# FOC.net
KiCad netlist of a schematic drawn in Altium Designer
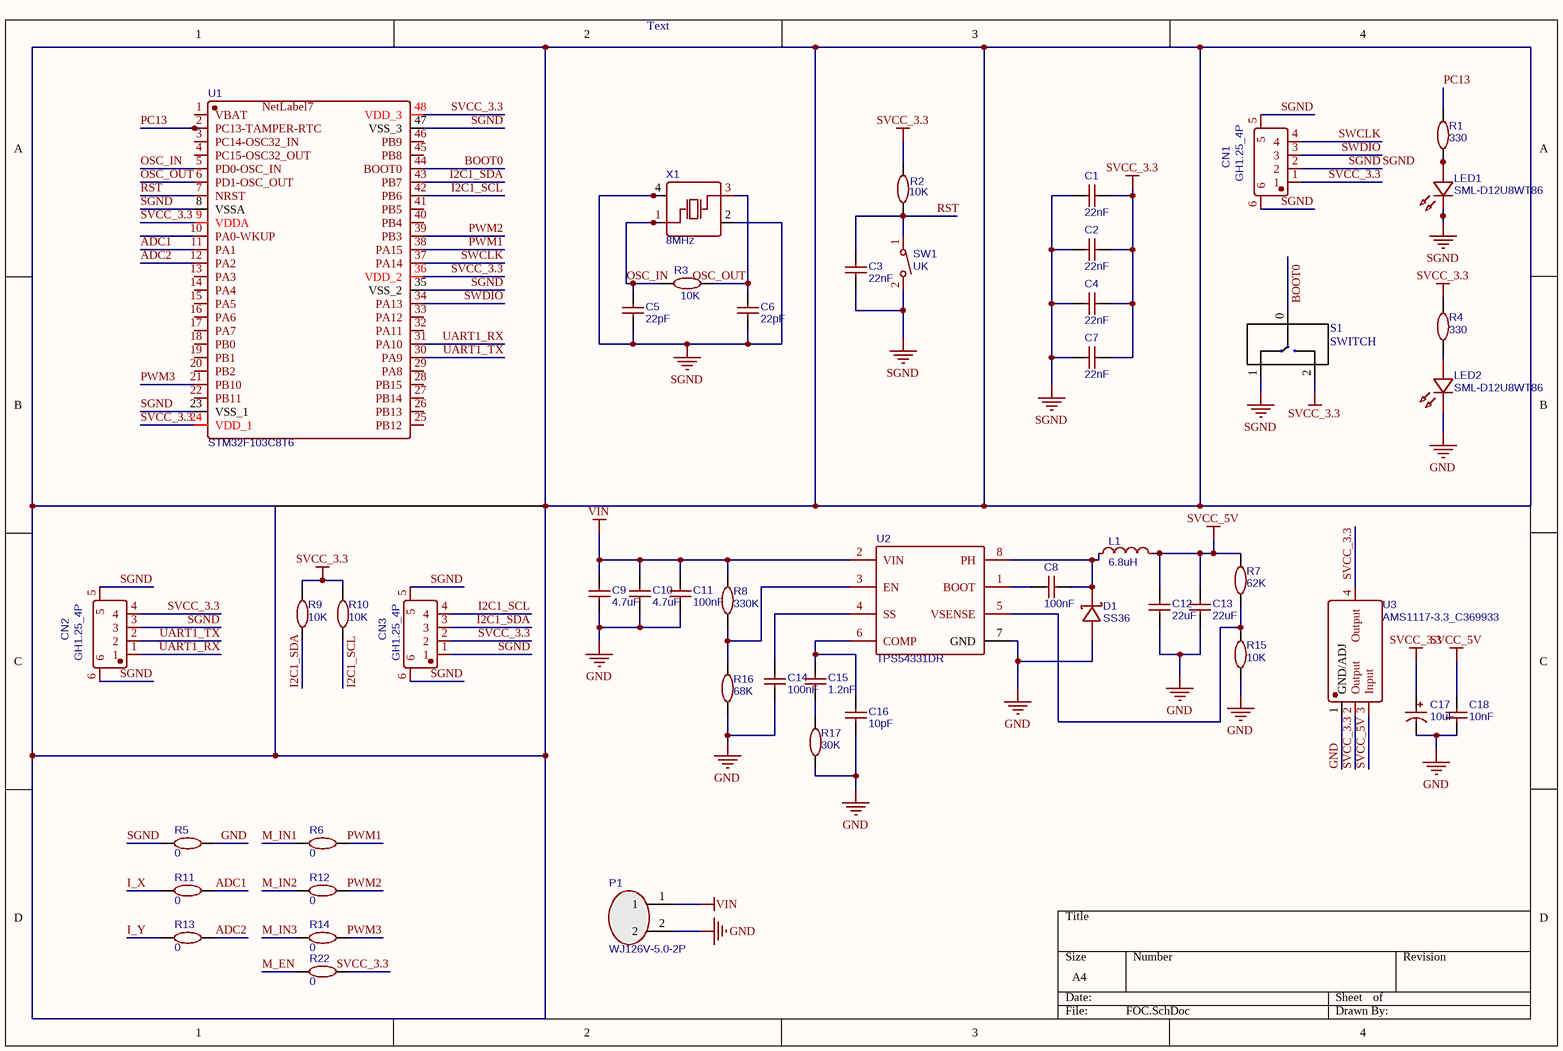
[diagram p0: FOC.SchDoc]

(export (version "E")
  (design (tool "Eeschema 10.0.6"))
  (components
    (comp (ref "C1")
      (value "22nF")
      (footprint "C0603")
      (fields
        (field (name "BOM_MANUFACTURER PART") "CC0805KRX7R9BB104")
        (field (name "BOM_SUPPLIER PART") "C49678")
      )
      (libsource (lib "FOC") (part "22nF"))
    )
    (comp (ref "C2")
      (value "22nF")
      (footprint "C0603")
      (fields
        (field (name "BOM_MANUFACTURER PART") "CC0805KRX7R9BB104")
        (field (name "BOM_SUPPLIER PART") "C49678")
      )
      (libsource (lib "FOC") (part "22nF"))
    )
    (comp (ref "C3")
      (value "22nF")
      (footprint "C0603")
      (fields
        (field (name "BOM_MANUFACTURER PART") "CC0805KRX7R9BB104")
        (field (name "BOM_SUPPLIER PART") "C49678")
      )
      (libsource (lib "FOC") (part "22nF"))
    )
    (comp (ref "C4")
      (value "22nF")
      (footprint "C0603")
      (fields
        (field (name "BOM_MANUFACTURER PART") "CC0805KRX7R9BB104")
        (field (name "BOM_SUPPLIER PART") "C49678")
      )
      (libsource (lib "FOC") (part "22nF"))
    )
    (comp (ref "C5")
      (value "22pF")
      (footprint "C0603")
      (fields
        (field (name "BOM_MANUFACTURER PART") "CC0805KRX7R9BB104")
        (field (name "BOM_SUPPLIER PART") "C49678")
      )
      (libsource (lib "FOC") (part "22pF"))
    )
    (comp (ref "C6")
      (value "22pF")
      (footprint "C0603")
      (fields
        (field (name "BOM_MANUFACTURER PART") "CC0805KRX7R9BB104")
        (field (name "BOM_SUPPLIER PART") "C49678")
      )
      (libsource (lib "FOC") (part "22pF"))
    )
    (comp (ref "C7")
      (value "22nF")
      (footprint "C0603")
      (fields
        (field (name "BOM_MANUFACTURER PART") "CC0805KRX7R9BB104")
        (field (name "BOM_SUPPLIER PART") "C49678")
      )
      (libsource (lib "FOC") (part "22nF"))
    )
    (comp (ref "C8")
      (value "100nF")
      (footprint "C0603")
      (fields
        (field (name "BOM_MANUFACTURER PART") "CC0805KRX7R9BB104")
        (field (name "BOM_SUPPLIER PART") "C49678")
      )
      (libsource (lib "FOC") (part "100nF"))
    )
    (comp (ref "C9")
      (value "4.7uF")
      (footprint "C0603")
      (fields
        (field (name "BOM_MANUFACTURER PART") "CC0805KRX7R9BB104")
        (field (name "BOM_SUPPLIER PART") "C49678")
      )
      (libsource (lib "FOC") (part "4.7uF"))
    )
    (comp (ref "C10")
      (value "4.7uF")
      (footprint "C0603")
      (fields
        (field (name "BOM_MANUFACTURER PART") "CC0805KRX7R9BB104")
        (field (name "BOM_SUPPLIER PART") "C49678")
      )
      (libsource (lib "FOC") (part "4.7uF"))
    )
    (comp (ref "C11")
      (value "100nF")
      (footprint "C0603")
      (fields
        (field (name "BOM_MANUFACTURER PART") "CC0805KRX7R9BB104")
        (field (name "BOM_SUPPLIER PART") "C49678")
      )
      (libsource (lib "FOC") (part "100nF"))
    )
    (comp (ref "C12")
      (value "22uF")
      (footprint "C0603")
      (fields
        (field (name "BOM_MANUFACTURER PART") "CC0805KRX7R9BB104")
        (field (name "BOM_SUPPLIER PART") "C49678")
      )
      (libsource (lib "FOC") (part "22uF"))
    )
    (comp (ref "C13")
      (value "22uF")
      (footprint "C0603")
      (fields
        (field (name "BOM_MANUFACTURER PART") "CC0805KRX7R9BB104")
        (field (name "BOM_SUPPLIER PART") "C49678")
      )
      (libsource (lib "FOC") (part "22uF"))
    )
    (comp (ref "C14")
      (value "100nF")
      (footprint "C0603")
      (fields
        (field (name "BOM_MANUFACTURER PART") "CC0805KRX7R9BB104")
        (field (name "BOM_SUPPLIER PART") "C49678")
      )
      (libsource (lib "FOC") (part "100nF"))
    )
    (comp (ref "C15")
      (value "1.2nF")
      (footprint "C0603")
      (fields
        (field (name "BOM_MANUFACTURER PART") "CC0805KRX7R9BB104")
        (field (name "BOM_SUPPLIER PART") "C49678")
      )
      (libsource (lib "FOC") (part "1.2nF"))
    )
    (comp (ref "C16")
      (value "10pF")
      (footprint "C0603")
      (fields
        (field (name "BOM_MANUFACTURER PART") "CC0805KRX7R9BB104")
        (field (name "BOM_SUPPLIER PART") "C49678")
      )
      (libsource (lib "FOC") (part "10pF"))
    )
    (comp (ref "C17")
      (value "10uF")
      (footprint "CAP-SMD_L3.2-W1.6-RD")
      (description "tan")
      (fields
        (field (name "BOM_MANUFACTURER PART") "CA45-A016K106T")
        (field (name "BOM_SUPPLIER PART") "C119051")
        (field (name "CONTRIBUTOR") "LCSC")
      )
      (libsource (lib "FOC") (part "10uF"))
    )
    (comp (ref "C18")
      (value "10nF")
      (footprint "C0603")
      (fields
        (field (name "BOM_MANUFACTURER PART") "CC0805KRX7R9BB104")
        (field (name "BOM_SUPPLIER PART") "C49678")
      )
      (libsource (lib "FOC") (part "10nF"))
    )
    (comp (ref "CN1")
      (value "GH1.25_4P")
      (footprint "CONN-TH_4P-P1.25_HRS_DF13-4P-1.25H-21")
      (fields
        (field (name "BOM_SUPPLIER PART") "C597872")
        (field (name "BOM_MANUFACTURER PART") "DF13-4P-1.25H(21)")
        (field (name "CONTRIBUTOR") "LCSC")
      )
      (libsource (lib "FOC") (part "GH1.25_4P"))
    )
    (comp (ref "CN2")
      (value "GH1.25_4P")
      (footprint "CONN-TH_4P-P1.25_HRS_DF13-4P-1.25H-21")
      (fields
        (field (name "BOM_SUPPLIER PART") "C597872")
        (field (name "BOM_MANUFACTURER PART") "DF13-4P-1.25H(21)")
        (field (name "CONTRIBUTOR") "LCSC")
      )
      (libsource (lib "FOC") (part "GH1.25_4P"))
    )
    (comp (ref "CN3")
      (value "GH1.25_4P")
      (footprint "CONN-TH_4P-P1.25_HRS_DF13-4P-1.25H-21")
      (fields
        (field (name "BOM_SUPPLIER PART") "C597872")
        (field (name "BOM_MANUFACTURER PART") "DF13-4P-1.25H(21)")
        (field (name "CONTRIBUTOR") "LCSC")
      )
      (libsource (lib "FOC") (part "GH1.25_4P"))
    )
    (comp (ref "D1")
      (value "SS36")
      (footprint "SMA_L4.3-W2.6-LS5.2-RD")
      (fields (field (name "BOM_SUPPLIER PART") "C16015"))
      (libsource (lib "FOC") (part "SS36"))
    )
    (comp (ref "L1")
      (value "6.8uH")
      (footprint "IND-SMD_L5.0-W5.0_SWPA5040S")
      (fields
        (field (name "BOM_MANUFACTURER PART") "SWPA5040S6R8M")
        (field (name "BOM_SUPPLIER PART") "C36411")
      )
      (libsource (lib "FOC") (part "6.8uH"))
    )
    (comp (ref "LED1")
      (value "SML-D12U8WT86")
      (footprint "LED0603-RD")
      (description "0603")
      (fields (field (name "BOM_SUPPLIER PART") "C510027") (field (name "CONTRIBUTOR") "LCSC"))
      (libsource (lib "FOC") (part "LED_1"))
    )
    (comp (ref "LED2")
      (value "SML-D12U8WT86")
      (footprint "LED0603-RD")
      (description "0603")
      (fields (field (name "BOM_SUPPLIER PART") "C510027") (field (name "CONTRIBUTOR") "LCSC"))
      (libsource (lib "FOC") (part "LED_1"))
    )
    (comp (ref "P1")
      (value "WJ126V-5.0-2P")
      (footprint "CONN-TH_WJ126V-5.0-2P")
      (fields (field (name "BOM_SUPPLIER PART") "C8404"))
      (libsource (lib "FOC") (part "WJ126V-5.0-2P"))
    )
    (comp (ref "R1")
      (value "330")
      (footprint "C0603")
      (fields
        (field (name "BOM_MANUFACTURER PART") "0805W8F1002T5E")
        (field (name "BOM_SUPPLIER PART") "C17414")
      )
      (libsource (lib "FOC") (part "330"))
    )
    (comp (ref "R2")
      (value "10K")
      (footprint "R0603")
      (fields
        (field (name "BOM_MANUFACTURER PART") "0805W8F1002T5E")
        (field (name "BOM_SUPPLIER PART") "C17414")
      )
      (libsource (lib "FOC") (part "10K"))
    )
    (comp (ref "R3")
      (value "10K")
      (footprint "R0603")
      (fields
        (field (name "BOM_MANUFACTURER PART") "0805W8F1002T5E")
        (field (name "BOM_SUPPLIER PART") "C17414")
      )
      (libsource (lib "FOC") (part "10K"))
    )
    (comp (ref "R4")
      (value "330")
      (footprint "C0603")
      (fields
        (field (name "BOM_MANUFACTURER PART") "0805W8F1002T5E")
        (field (name "BOM_SUPPLIER PART") "C17414")
      )
      (libsource (lib "FOC") (part "330"))
    )
    (comp (ref "R5")
      (value "0")
      (footprint "R0603")
      (description "0欧电阻")
      (fields
        (field (name "BOM_MANUFACTURER PART") "0805W8F1002T5E")
        (field (name "BOM_SUPPLIER PART") "C17414")
      )
      (libsource (lib "FOC") (part "0"))
    )
    (comp (ref "R6")
      (value "0")
      (footprint "R0603")
      (description "0欧电阻")
      (fields
        (field (name "BOM_MANUFACTURER PART") "0805W8F1002T5E")
        (field (name "BOM_SUPPLIER PART") "C17414")
      )
      (libsource (lib "FOC") (part "0"))
    )
    (comp (ref "R7")
      (value "62K")
      (footprint "R0603")
      (fields
        (field (name "BOM_MANUFACTURER PART") "0805W8F1002T5E")
        (field (name "BOM_SUPPLIER PART") "C17414")
      )
      (libsource (lib "FOC") (part "62K"))
    )
    (comp (ref "R8")
      (value "330K")
      (footprint "R0603")
      (description "R0603")
      (fields
        (field (name "BOM_MANUFACTURER PART") "0603WAF3303T5E")
        (field (name "BOM_SUPPLIER PART") "C23137")
      )
      (libsource (lib "FOC") (part "330K"))
    )
    (comp (ref "R9")
      (value "10K")
      (footprint "R0603")
      (fields
        (field (name "BOM_MANUFACTURER PART") "0805W8F1002T5E")
        (field (name "BOM_SUPPLIER PART") "C17414")
      )
      (libsource (lib "FOC") (part "10K"))
    )
    (comp (ref "R10")
      (value "10K")
      (footprint "R0603")
      (fields
        (field (name "BOM_MANUFACTURER PART") "0805W8F1002T5E")
        (field (name "BOM_SUPPLIER PART") "C17414")
      )
      (libsource (lib "FOC") (part "10K"))
    )
    (comp (ref "R11")
      (value "0")
      (footprint "R0603")
      (description "0欧电阻")
      (fields
        (field (name "BOM_MANUFACTURER PART") "0805W8F1002T5E")
        (field (name "BOM_SUPPLIER PART") "C17414")
      )
      (libsource (lib "FOC") (part "0"))
    )
    (comp (ref "R12")
      (value "0")
      (footprint "R0603")
      (description "0欧电阻")
      (fields
        (field (name "BOM_MANUFACTURER PART") "0805W8F1002T5E")
        (field (name "BOM_SUPPLIER PART") "C17414")
      )
      (libsource (lib "FOC") (part "0"))
    )
    (comp (ref "R13")
      (value "0")
      (footprint "R0603")
      (description "0欧电阻")
      (fields
        (field (name "BOM_MANUFACTURER PART") "0805W8F1002T5E")
        (field (name "BOM_SUPPLIER PART") "C17414")
      )
      (libsource (lib "FOC") (part "0"))
    )
    (comp (ref "R14")
      (value "0")
      (footprint "R0603")
      (description "0欧电阻")
      (fields
        (field (name "BOM_MANUFACTURER PART") "0805W8F1002T5E")
        (field (name "BOM_SUPPLIER PART") "C17414")
      )
      (libsource (lib "FOC") (part "0"))
    )
    (comp (ref "R15")
      (value "10K")
      (footprint "R0603")
      (fields
        (field (name "BOM_MANUFACTURER PART") "0805W8F1002T5E")
        (field (name "BOM_SUPPLIER PART") "C17414")
      )
      (libsource (lib "FOC") (part "10K"))
    )
    (comp (ref "R16")
      (value "68K")
      (footprint "R0603")
      (fields
        (field (name "BOM_MANUFACTURER PART") "0805W8F1002T5E")
        (field (name "BOM_SUPPLIER PART") "C17414")
      )
      (libsource (lib "FOC") (part "68K"))
    )
    (comp (ref "R17")
      (value "30K")
      (footprint "R0603")
      (fields
        (field (name "BOM_MANUFACTURER PART") "0805W8F1002T5E")
        (field (name "BOM_SUPPLIER PART") "C17414")
      )
      (libsource (lib "FOC") (part "30K"))
    )
    (comp (ref "R22")
      (value "0")
      (footprint "R0603")
      (description "0欧电阻")
      (fields
        (field (name "BOM_MANUFACTURER PART") "0805W8F1002T5E")
        (field (name "BOM_SUPPLIER PART") "C17414")
      )
      (libsource (lib "FOC") (part "0"))
    )
    (comp (ref "S1") (value "SWITCH") (footprint "switch") (libsource (lib "FOC") (part "SWITCH")))
    (comp (ref "SW1")
      (value "UK")
      (footprint "SW-TH_L6.0-W3.5-P6.50")
      (fields
        (field (name "BOM_SUPPLIER PART") "C493223")
        (field (name "BOM_MANUFACTURER PART") "UK-B0205G43-DP25Y")
        (field (name "CONTRIBUTOR") "LCSC")
      )
      (libsource (lib "FOC") (part "UK-B0205G43-DP25Y"))
    )
    (comp (ref "U1")
      (value "STM32F103C8T6")
      (footprint "LQFP-48_L7.0-W7.0-P0.50-LS9.0-BL")
      (fields (field (name "BOM_SUPPLIER PART") "C8734"))
      (libsource (lib "FOC") (part "STM32F103C8T6"))
    )
    (comp (ref "U2")
      (value "TPS54331DR")
      (footprint "SOIC-8_L5.0-W4.0-P1.27-LS6.0-BL")
      (description "电源芯片")
      (fields (field (name "BOM_SUPPLIER PART") "C9865"))
      (libsource (lib "FOC") (part "TPS54331DR"))
    )
    (comp (ref "U3")
      (value "AMS1117-3.3_C369933")
      (footprint "SOT-223-4_L6.5-W3.5-P2.30-LS7.0-BR")
      (fields
        (field (name "BOM_SUPPLIER PART") "C369933")
        (field (name "BOM_MANUFACTURER PART") "AMS1117-3.3")
        (field (name "CONTRIBUTOR") "LCSC")
      )
      (libsource (lib "FOC") (part "AMS1117-3.3_C369933"))
    )
    (comp (ref "X1")
      (value "8MHz")
      (footprint "CRYSTAL-SMD_4P-L5.0-W3.2-BL")
      (fields
        (field (name "BOM_SUPPLIER PART") "C337573")
        (field (name "BOM_MANUFACTURER PART") "7B08070003")
        (field (name "CONTRIBUTOR") "LCSC")
      )
      (libsource (lib "FOC") (part "8MHz"))
    )
  )
  (nets
    (net (code "1") (name "/ADC1") (class "Default")
      (node (ref "R11") (pin "2") (pinfunction "2_2") (pintype "passive"))
      (node (ref "U1") (pin "11") (pinfunction "PA1_11") (pintype "passive"))
    )
    (net (code "2") (name "/ADC2") (class "Default")
      (node (ref "R13") (pin "2") (pinfunction "2_2") (pintype "passive"))
      (node (ref "U1") (pin "12") (pinfunction "PA2_12") (pintype "passive"))
    )
    (net (code "3") (name "/BOOT0") (class "Default")
      (node (ref "S1") (pin "0") (pinfunction "0_0") (pintype "passive"))
      (node (ref "U1") (pin "44") (pinfunction "BOOT0_44") (pintype "passive"))
    )
    (net (code "4") (name "/I2C1_SCL") (class "Default")
      (node (ref "CN3") (pin "4") (pinfunction "4_4") (pintype "passive"))
      (node (ref "R10") (pin "1") (pinfunction "1_1") (pintype "passive"))
      (node (ref "U1") (pin "42") (pinfunction "PB6_42") (pintype "passive"))
    )
    (net (code "5") (name "/I2C1_SDA") (class "Default")
      (node (ref "CN3") (pin "3") (pinfunction "3_3") (pintype "passive"))
      (node (ref "R9") (pin "1") (pinfunction "1_1") (pintype "passive"))
      (node (ref "U1") (pin "43") (pinfunction "PB7_43") (pintype "passive"))
    )
    (net (code "6") (name "/I_X") (class "Default")
      (node (ref "R11") (pin "1") (pinfunction "1_1") (pintype "passive"))
    )
    (net (code "7") (name "/I_Y") (class "Default")
      (node (ref "R13") (pin "1") (pinfunction "1_1") (pintype "passive"))
    )
    (net (code "8") (name "/M_EN") (class "Default")
      (node (ref "R22") (pin "1") (pinfunction "1_1") (pintype "passive"))
    )
    (net (code "9") (name "/M_IN1") (class "Default")
      (node (ref "R6") (pin "1") (pinfunction "1_1") (pintype "passive"))
    )
    (net (code "10") (name "/M_IN2") (class "Default")
      (node (ref "R12") (pin "1") (pinfunction "1_1") (pintype "passive"))
    )
    (net (code "11") (name "/M_IN3") (class "Default")
      (node (ref "R14") (pin "1") (pinfunction "1_1") (pintype "passive"))
    )
    (net (code "13") (name "/OSC_IN") (class "Default")
      (node (ref "C5") (pin "2") (pinfunction "2_2") (pintype "passive"))
      (node (ref "R3") (pin "1") (pinfunction "1_1") (pintype "passive"))
      (node (ref "U1") (pin "5") (pinfunction "PD0-OSC_IN_5") (pintype "passive"))
      (node (ref "X1") (pin "1") (pinfunction "OSC1_1") (pintype "passive"))
    )
    (net (code "14") (name "/OSC_OUT") (class "Default")
      (node (ref "C6") (pin "2") (pinfunction "2_2") (pintype "passive"))
      (node (ref "R3") (pin "2") (pinfunction "2_2") (pintype "passive"))
      (node (ref "U1") (pin "6") (pinfunction "PD1-OSC_OUT_6") (pintype "passive"))
      (node (ref "X1") (pin "3") (pinfunction "OSC2_3") (pintype "passive"))
    )
    (net (code "15") (name "/PC13") (class "Default")
      (node (ref "R1") (pin "2") (pinfunction "2_2") (pintype "passive"))
      (node (ref "U1") (pin "2") (pinfunction "PC13-TAMPER-RTC_2") (pintype "passive"))
    )
    (net (code "16") (name "/PWM1") (class "Default")
      (node (ref "R6") (pin "2") (pinfunction "2_2") (pintype "passive"))
      (node (ref "U1") (pin "38") (pinfunction "PA15_38") (pintype "passive"))
    )
    (net (code "17") (name "/PWM2") (class "Default")
      (node (ref "R12") (pin "2") (pinfunction "2_2") (pintype "passive"))
      (node (ref "U1") (pin "39") (pinfunction "PB3_39") (pintype "passive"))
    )
    (net (code "18") (name "/PWM3") (class "Default")
      (node (ref "R14") (pin "2") (pinfunction "2_2") (pintype "passive"))
      (node (ref "U1") (pin "21") (pinfunction "PB10_21") (pintype "passive"))
    )
    (net (code "19") (name "/RST") (class "Default")
      (node (ref "C3") (pin "2") (pinfunction "2_2") (pintype "passive"))
      (node (ref "R2") (pin "2") (pinfunction "2_2") (pintype "passive"))
      (node (ref "SW1") (pin "1") (pinfunction "1_1") (pintype "passive"))
      (node (ref "U1") (pin "7") (pinfunction "NRST_7") (pintype "passive"))
    )
    (net (code "20") (name "/SWCLK") (class "Default")
      (node (ref "CN1") (pin "4") (pinfunction "4_4") (pintype "passive"))
      (node (ref "U1") (pin "37") (pinfunction "PA14_37") (pintype "passive"))
    )
    (net (code "21") (name "/SWDIO") (class "Default")
      (node (ref "CN1") (pin "3") (pinfunction "3_3") (pintype "passive"))
      (node (ref "U1") (pin "34") (pinfunction "PA13_34") (pintype "passive"))
    )
    (net (code "22") (name "/UART1_RX") (class "Default")
      (node (ref "CN2") (pin "1") (pinfunction "1_1") (pintype "passive"))
      (node (ref "U1") (pin "31") (pinfunction "PA10_31") (pintype "passive"))
    )
    (net (code "23") (name "/UART1_TX") (class "Default")
      (node (ref "CN2") (pin "2") (pinfunction "2_2") (pintype "passive"))
      (node (ref "U1") (pin "30") (pinfunction "PA9_30") (pintype "passive"))
    )
    (net (code "24") (name "GND") (class "Default")
      (node (ref "C10") (pin "1") (pinfunction "1_1") (pintype "passive"))
      (node (ref "C11") (pin "1") (pinfunction "1_1") (pintype "passive"))
      (node (ref "C12") (pin "1") (pinfunction "1_1") (pintype "passive"))
      (node (ref "C13") (pin "1") (pinfunction "1_1") (pintype "passive"))
      (node (ref "C14") (pin "1") (pinfunction "1_1") (pintype "passive"))
      (node (ref "C16") (pin "1") (pinfunction "1_1") (pintype "passive"))
      (node (ref "C17") (pin "2") (pinfunction "2_2") (pintype "passive"))
      (node (ref "C18") (pin "1") (pinfunction "1_1") (pintype "passive"))
      (node (ref "C9") (pin "1") (pinfunction "1_1") (pintype "passive"))
      (node (ref "D1") (pin "2") (pinfunction "A_2") (pintype "passive"))
      (node (ref "LED2") (pin "1") (pinfunction "K_1") (pintype "passive"))
      (node (ref "P1") (pin "2") (pinfunction "2_2") (pintype "passive"))
      (node (ref "R15") (pin "1") (pinfunction "1_1") (pintype "passive"))
      (node (ref "R16") (pin "1") (pinfunction "1_1") (pintype "passive"))
      (node (ref "R17") (pin "1") (pinfunction "1_1") (pintype "passive"))
      (node (ref "R5") (pin "2") (pinfunction "2_2") (pintype "passive"))
      (node (ref "U2") (pin "7") (pinfunction "GND_7") (pintype "passive"))
      (node (ref "U3") (pin "1") (pinfunction "GND/ADJ_1") (pintype "passive"))
    )
    (net (code "25") (name "Net-(C15-Pad1)") (class "Default")
      (node (ref "C15") (pin "1") (pinfunction "1_1") (pintype "passive"))
      (node (ref "R17") (pin "2") (pinfunction "2_2") (pintype "passive"))
    )
    (net (code "26") (name "Net-(D1-K)") (class "Default")
      (node (ref "C8") (pin "1") (pinfunction "1_1") (pintype "passive"))
      (node (ref "D1") (pin "1") (pinfunction "K_1") (pintype "passive"))
      (node (ref "L1") (pin "1") (pinfunction "1_1") (pintype "passive"))
      (node (ref "U2") (pin "8") (pinfunction "PH_8") (pintype "passive"))
    )
    (net (code "27") (name "Net-(LED1-A)") (class "Default")
      (node (ref "LED1") (pin "2") (pinfunction "A_2") (pintype "passive"))
      (node (ref "R1") (pin "1") (pinfunction "1_1") (pintype "passive"))
    )
    (net (code "28") (name "Net-(LED2-A)") (class "Default")
      (node (ref "LED2") (pin "2") (pinfunction "A_2") (pintype "passive"))
      (node (ref "R4") (pin "1") (pinfunction "1_1") (pintype "passive"))
    )
    (net (code "29") (name "Net-(U2-BOOT)") (class "Default")
      (node (ref "C8") (pin "2") (pinfunction "2_2") (pintype "passive"))
      (node (ref "U2") (pin "1") (pinfunction "BOOT_1") (pintype "passive"))
    )
    (net (code "30") (name "Net-(U2-COMP)") (class "Default")
      (node (ref "C15") (pin "2") (pinfunction "2_2") (pintype "passive"))
      (node (ref "C16") (pin "2") (pinfunction "2_2") (pintype "passive"))
      (node (ref "U2") (pin "6") (pinfunction "COMP_6") (pintype "passive"))
    )
    (net (code "31") (name "Net-(U2-EN)") (class "Default")
      (node (ref "R16") (pin "2") (pinfunction "2_2") (pintype "passive"))
      (node (ref "R8") (pin "1") (pinfunction "1_1") (pintype "passive"))
      (node (ref "U2") (pin "3") (pinfunction "EN_3") (pintype "passive"))
    )
    (net (code "32") (name "Net-(U2-SS)") (class "Default")
      (node (ref "C14") (pin "2") (pinfunction "2_2") (pintype "passive"))
      (node (ref "U2") (pin "4") (pinfunction "SS_4") (pintype "passive"))
    )
    (net (code "33") (name "Net-(U2-VSENSE)") (class "Default")
      (node (ref "R15") (pin "2") (pinfunction "2_2") (pintype "passive"))
      (node (ref "R7") (pin "1") (pinfunction "1_1") (pintype "passive"))
      (node (ref "U2") (pin "5") (pinfunction "VSENSE_5") (pintype "passive"))
    )
    (net (code "34") (name "SGND") (class "Default")
      (node (ref "C1") (pin "1") (pinfunction "1_1") (pintype "passive"))
      (node (ref "C2") (pin "1") (pinfunction "1_1") (pintype "passive"))
      (node (ref "C3") (pin "1") (pinfunction "1_1") (pintype "passive"))
      (node (ref "C4") (pin "1") (pinfunction "1_1") (pintype "passive"))
      (node (ref "C5") (pin "1") (pinfunction "1_1") (pintype "passive"))
      (node (ref "C6") (pin "1") (pinfunction "1_1") (pintype "passive"))
      (node (ref "C7") (pin "1") (pinfunction "1_1") (pintype "passive"))
      (node (ref "CN1") (pin "2") (pinfunction "2_2") (pintype "passive"))
      (node (ref "CN1") (pin "5") (pinfunction "5_5") (pintype "passive"))
      (node (ref "CN1") (pin "6") (pinfunction "6_6") (pintype "passive"))
      (node (ref "CN2") (pin "3") (pinfunction "3_3") (pintype "passive"))
      (node (ref "CN2") (pin "5") (pinfunction "5_5") (pintype "passive"))
      (node (ref "CN2") (pin "6") (pinfunction "6_6") (pintype "passive"))
      (node (ref "CN3") (pin "1") (pinfunction "1_1") (pintype "passive"))
      (node (ref "CN3") (pin "5") (pinfunction "5_5") (pintype "passive"))
      (node (ref "CN3") (pin "6") (pinfunction "6_6") (pintype "passive"))
      (node (ref "LED1") (pin "1") (pinfunction "K_1") (pintype "passive"))
      (node (ref "R5") (pin "1") (pinfunction "1_1") (pintype "passive"))
      (node (ref "S1") (pin "1") (pinfunction "1_1") (pintype "passive"))
      (node (ref "SW1") (pin "2") (pinfunction "2_2") (pintype "passive"))
      (node (ref "U1") (pin "23") (pinfunction "VSS_1_23") (pintype "passive"))
      (node (ref "U1") (pin "35") (pinfunction "VSS_2_35") (pintype "passive"))
      (node (ref "U1") (pin "47") (pinfunction "VSS_3_47") (pintype "passive"))
      (node (ref "U1") (pin "8") (pinfunction "VSSA_8") (pintype "passive"))
      (node (ref "X1") (pin "2") (pinfunction "GND_2") (pintype "passive"))
      (node (ref "X1") (pin "4") (pinfunction "GND_4") (pintype "passive"))
    )
    (net (code "35") (name "SVCC_3.3") (class "Default")
      (node (ref "C1") (pin "2") (pinfunction "2_2") (pintype "passive"))
      (node (ref "C17") (pin "1") (pinfunction "1_1") (pintype "passive"))
      (node (ref "C2") (pin "2") (pinfunction "2_2") (pintype "passive"))
      (node (ref "C4") (pin "2") (pinfunction "2_2") (pintype "passive"))
      (node (ref "C7") (pin "2") (pinfunction "2_2") (pintype "passive"))
      (node (ref "CN1") (pin "1") (pinfunction "1_1") (pintype "passive"))
      (node (ref "CN2") (pin "4") (pinfunction "4_4") (pintype "passive"))
      (node (ref "CN3") (pin "2") (pinfunction "2_2") (pintype "passive"))
      (node (ref "R10") (pin "2") (pinfunction "2_2") (pintype "passive"))
      (node (ref "R2") (pin "1") (pinfunction "1_1") (pintype "passive"))
      (node (ref "R22") (pin "2") (pinfunction "2_2") (pintype "passive"))
      (node (ref "R4") (pin "2") (pinfunction "2_2") (pintype "passive"))
      (node (ref "R9") (pin "2") (pinfunction "2_2") (pintype "passive"))
      (node (ref "S1") (pin "2") (pinfunction "2_2") (pintype "passive"))
      (node (ref "U1") (pin "24") (pinfunction "VDD_1_24") (pintype "passive"))
      (node (ref "U1") (pin "36") (pinfunction "VDD_2_36") (pintype "passive"))
      (node (ref "U1") (pin "48") (pinfunction "VDD_3_48") (pintype "passive"))
      (node (ref "U1") (pin "9") (pinfunction "VDDA_9") (pintype "passive"))
      (node (ref "U3") (pin "2") (pinfunction "Output_2") (pintype "passive"))
      (node (ref "U3") (pin "4") (pinfunction "Output_4") (pintype "passive"))
    )
    (net (code "36") (name "SVCC_5V") (class "Default")
      (node (ref "C12") (pin "2") (pinfunction "2_2") (pintype "passive"))
      (node (ref "C13") (pin "2") (pinfunction "2_2") (pintype "passive"))
      (node (ref "C18") (pin "2") (pinfunction "2_2") (pintype "passive"))
      (node (ref "L1") (pin "2") (pinfunction "2_2") (pintype "passive"))
      (node (ref "R7") (pin "2") (pinfunction "2_2") (pintype "passive"))
      (node (ref "U3") (pin "3") (pinfunction "Input_3") (pintype "passive"))
    )
    (net (code "37") (name "VIN") (class "Default")
      (node (ref "C10") (pin "2") (pinfunction "2_2") (pintype "passive"))
      (node (ref "C11") (pin "2") (pinfunction "2_2") (pintype "passive"))
      (node (ref "C9") (pin "2") (pinfunction "2_2") (pintype "passive"))
      (node (ref "P1") (pin "1") (pinfunction "1_1") (pintype "passive"))
      (node (ref "R8") (pin "2") (pinfunction "2_2") (pintype "passive"))
      (node (ref "U2") (pin "2") (pinfunction "VIN_2") (pintype "passive"))
    )
    (net (code "38") (name "unconnected-(U1-PA0-WKUP-Pad10)") (class "Default")
      (node (ref "U1") (pin "10") (pinfunction "PA0-WKUP_10") (pintype "passive"))
    )
    (net (code "39") (name "unconnected-(U1-PA3-Pad13)") (class "Default")
      (node (ref "U1") (pin "13") (pinfunction "PA3_13") (pintype "passive"))
    )
    (net (code "40") (name "unconnected-(U1-PA4-Pad14)") (class "Default")
      (node (ref "U1") (pin "14") (pinfunction "PA4_14") (pintype "passive"))
    )
    (net (code "41") (name "unconnected-(U1-PA5-Pad15)") (class "Default")
      (node (ref "U1") (pin "15") (pinfunction "PA5_15") (pintype "passive"))
    )
    (net (code "42") (name "unconnected-(U1-PA6-Pad16)") (class "Default")
      (node (ref "U1") (pin "16") (pinfunction "PA6_16") (pintype "passive"))
    )
    (net (code "43") (name "unconnected-(U1-PA7-Pad17)") (class "Default")
      (node (ref "U1") (pin "17") (pinfunction "PA7_17") (pintype "passive"))
    )
    (net (code "44") (name "unconnected-(U1-PA8-Pad29)") (class "Default")
      (node (ref "U1") (pin "29") (pinfunction "PA8_29") (pintype "passive"))
    )
    (net (code "45") (name "unconnected-(U1-PA11-Pad32)") (class "Default")
      (node (ref "U1") (pin "32") (pinfunction "PA11_32") (pintype "passive"))
    )
    (net (code "46") (name "unconnected-(U1-PA12-Pad33)") (class "Default")
      (node (ref "U1") (pin "33") (pinfunction "PA12_33") (pintype "passive"))
    )
    (net (code "47") (name "unconnected-(U1-PB0-Pad18)") (class "Default")
      (node (ref "U1") (pin "18") (pinfunction "PB0_18") (pintype "passive"))
    )
    (net (code "48") (name "unconnected-(U1-PB1-Pad19)") (class "Default")
      (node (ref "U1") (pin "19") (pinfunction "PB1_19") (pintype "passive"))
    )
    (net (code "49") (name "unconnected-(U1-PB2-Pad20)") (class "Default")
      (node (ref "U1") (pin "20") (pinfunction "PB2_20") (pintype "passive"))
    )
    (net (code "50") (name "unconnected-(U1-PB4-Pad40)") (class "Default")
      (node (ref "U1") (pin "40") (pinfunction "PB4_40") (pintype "passive"))
    )
    (net (code "51") (name "unconnected-(U1-PB5-Pad41)") (class "Default")
      (node (ref "U1") (pin "41") (pinfunction "PB5_41") (pintype "passive"))
    )
    (net (code "52") (name "unconnected-(U1-PB8-Pad45)") (class "Default")
      (node (ref "U1") (pin "45") (pinfunction "PB8_45") (pintype "passive"))
    )
    (net (code "53") (name "unconnected-(U1-PB9-Pad46)") (class "Default")
      (node (ref "U1") (pin "46") (pinfunction "PB9_46") (pintype "passive"))
    )
    (net (code "54") (name "unconnected-(U1-PB11-Pad22)") (class "Default")
      (node (ref "U1") (pin "22") (pinfunction "PB11_22") (pintype "passive"))
    )
    (net (code "55") (name "unconnected-(U1-PB12-Pad25)") (class "Default")
      (node (ref "U1") (pin "25") (pinfunction "PB12_25") (pintype "passive"))
    )
    (net (code "56") (name "unconnected-(U1-PB13-Pad26)") (class "Default")
      (node (ref "U1") (pin "26") (pinfunction "PB13_26") (pintype "passive"))
    )
    (net (code "57") (name "unconnected-(U1-PB14-Pad27)") (class "Default")
      (node (ref "U1") (pin "27") (pinfunction "PB14_27") (pintype "passive"))
    )
    (net (code "58") (name "unconnected-(U1-PB15-Pad28)") (class "Default")
      (node (ref "U1") (pin "28") (pinfunction "PB15_28") (pintype "passive"))
    )
    (net (code "59") (name "unconnected-(U1-PC14-OSC32_IN-Pad3)") (class "Default")
      (node (ref "U1") (pin "3") (pinfunction "PC14-OSC32_IN_3") (pintype "passive"))
    )
    (net (code "60") (name "unconnected-(U1-PC15-OSC32_OUT-Pad4)") (class "Default")
      (node (ref "U1") (pin "4") (pinfunction "PC15-OSC32_OUT_4") (pintype "passive"))
    )
    (net (code "61") (name "unconnected-(U1-VBAT-Pad1)") (class "Default")
      (node (ref "U1") (pin "1") (pinfunction "VBAT_1") (pintype "passive"))
    )
  )
)
